# 1_V5.net
KiCad netlist of a schematic drawn in Altium Designer
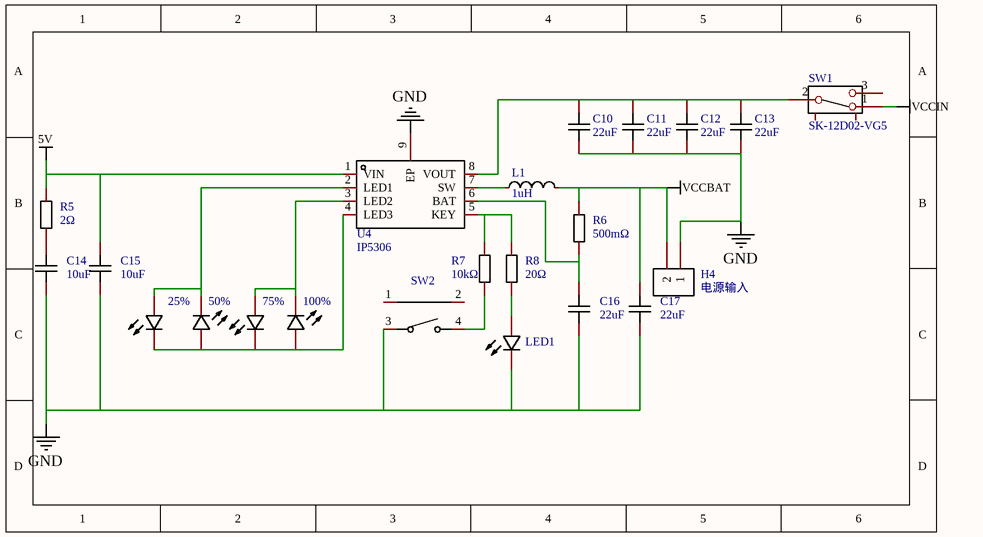
[diagram p0: 1_V5.schdoc]

(export (version "E")
  (design (tool "Eeschema 10.0.6"))
  (components
    (comp (ref "25%")
      (value "19-217/GHC-YR1S2/3T")
      (description "发光颜色:翠绿;二极管配置:-;主波长:520nm~535nm;色温:-;功率:110mW;安装方式:-;")
      (fields (field (name "MANUFACTURER") "EVERLIGHT(亿光)"))
      (libsource (lib "altium-import") (part "root_1_19-217/GHC-YR1S2/3T_"))
    )
    (comp (ref "50%")
      (value "19-217/GHC-YR1S2/3T")
      (description "发光颜色:翠绿;二极管配置:-;主波长:520nm~535nm;色温:-;功率:110mW;安装方式:-;")
      (fields (field (name "MANUFACTURER") "EVERLIGHT(亿光)"))
      (libsource (lib "altium-import") (part "root_3_19-217/GHC-YR1S2/3T_"))
    )
    (comp (ref "75%")
      (value "19-217/GHC-YR1S2/3T")
      (description "发光颜色:翠绿;二极管配置:-;主波长:520nm~535nm;色温:-;功率:110mW;安装方式:-;")
      (fields (field (name "MANUFACTURER") "EVERLIGHT(亿光)"))
      (libsource (lib "altium-import") (part "root_1_19-217/GHC-YR1S2/3T_"))
    )
    (comp (ref "100%")
      (value "19-217/GHC-YR1S2/3T")
      (description "发光颜色:翠绿;二极管配置:-;主波长:520nm~535nm;色温:-;功率:110mW;安装方式:-;")
      (fields (field (name "MANUFACTURER") "EVERLIGHT(亿光)"))
      (libsource (lib "altium-import") (part "root_3_19-217/GHC-YR1S2/3T_"))
    )
    (comp (ref "C10")
      (value "22uF")
      (description "容值:22uF;精度:±20%;额定电压:35V;材质(温度系数):X5R;")
      (fields
        (field (name "NAME") "22uF")
        (field (name "MANUFACTURER") "TDK")
        (field (name "MANUFACTURER PART") "C3216X5R1V226MTJ00E")
      )
      (libsource (lib "altium-import") (part "root_0_C3216X5R1V226MTJ00E_"))
    )
    (comp (ref "C11")
      (value "22uF")
      (description "容值:22uF;精度:±20%;额定电压:35V;材质(温度系数):X5R;")
      (fields
        (field (name "NAME") "22uF")
        (field (name "MANUFACTURER") "TDK")
        (field (name "MANUFACTURER PART") "C3216X5R1V226MTJ00E")
      )
      (libsource (lib "altium-import") (part "root_0_C3216X5R1V226MTJ00E_"))
    )
    (comp (ref "C12")
      (value "22uF")
      (description "容值:22uF;精度:±20%;额定电压:35V;材质(温度系数):X5R;")
      (fields
        (field (name "NAME") "22uF")
        (field (name "MANUFACTURER") "TDK")
        (field (name "MANUFACTURER PART") "C3216X5R1V226MTJ00E")
      )
      (libsource (lib "altium-import") (part "root_0_C3216X5R1V226MTJ00E_"))
    )
    (comp (ref "C13")
      (value "22uF")
      (description "容值:22uF;精度:±20%;额定电压:35V;材质(温度系数):X5R;")
      (fields
        (field (name "NAME") "22uF")
        (field (name "MANUFACTURER") "TDK")
        (field (name "MANUFACTURER PART") "C3216X5R1V226MTJ00E")
      )
      (libsource (lib "altium-import") (part "root_0_C3216X5R1V226MTJ00E_"))
    )
    (comp (ref "C14")
      (value "10uF")
      (description "容值:10uF;精度:±10%;额定电压:50V;材质(温度系数):X5R;")
      (fields
        (field (name "NAME") "10uF")
        (field (name "MANUFACTURER") "muRata(村田)")
        (field (name "MANUFACTURER PART") "GRM21BR61H106KE43L")
      )
      (libsource (lib "altium-import") (part "root_1_GRM21BR61H106KE43L_"))
    )
    (comp (ref "C15")
      (value "10uF")
      (description "容值:10uF;精度:±10%;额定电压:50V;材质(温度系数):X5R;")
      (fields
        (field (name "NAME") "10uF")
        (field (name "MANUFACTURER") "muRata(村田)")
        (field (name "MANUFACTURER PART") "GRM21BR61H106KE43L")
      )
      (libsource (lib "altium-import") (part "root_1_GRM21BR61H106KE43L_"))
    )
    (comp (ref "C16")
      (value "22uF")
      (description "容值:22uF;精度:±20%;额定电压:35V;材质(温度系数):X5R;")
      (fields
        (field (name "NAME") "22uF")
        (field (name "MANUFACTURER") "TDK")
        (field (name "MANUFACTURER PART") "C3216X5R1V226MTJ00E")
      )
      (libsource (lib "altium-import") (part "root_0_C3216X5R1V226MTJ00E_"))
    )
    (comp (ref "C17")
      (value "22uF")
      (description "容值:22uF;精度:±20%;额定电压:35V;材质(温度系数):X5R;")
      (fields
        (field (name "NAME") "22uF")
        (field (name "MANUFACTURER") "TDK")
        (field (name "MANUFACTURER PART") "C3216X5R1V226MTJ00E")
      )
      (libsource (lib "altium-import") (part "root_0_C3216X5R1V226MTJ00E_"))
    )
    (comp (ref "H4")
      (value "电源输入")
      (fields
        (field (name "NAME") "电源输入")
        (field (name "MANUFACTURER") "TE Connectivity(美国泰科)")
        (field (name "MANUFACTURER PART") "3-644456-2")
      )
      (libsource (lib "altium-import") (part "root_3_电源端口_"))
    )
    (comp (ref "L1")
      (value "1uH")
      (description "电感值:1uH;精度:±20%;额定电流:8.5A;饱和电流(Isat):14A;")
      (fields
        (field (name "NAME") "1uH")
        (field (name "MANUFACTURER") "cjiang(长江微电)")
        (field (name "MANUFACTURER PART") "FXL0618-1R0-M")
      )
      (libsource (lib "altium-import") (part "root_0_FXL0618-1R0-M_"))
    )
    (comp (ref "LED1")
      (value "19-217/GHC-YR1S2/3T")
      (description "发光颜色:翠绿;二极管配置:-;主波长:520nm~535nm;色温:-;功率:110mW;安装方式:-;")
      (fields (field (name "MANUFACTURER") "EVERLIGHT(亿光)"))
      (libsource (lib "altium-import") (part "root_1_19-217/GHC-YR1S2/3T_"))
    )
    (comp (ref "R5")
      (value "2Ω")
      (description "电阻类型:厚膜电阻;阻值:2Ω;精度:±1%;功率:125mW;")
      (fields
        (field (name "NAME") "2Ω")
        (field (name "MANUFACTURER") "UNI-ROYAL(厚声)")
        (field (name "MANUFACTURER PART") "0805W8F200KT5E")
      )
      (libsource (lib "altium-import") (part "root_1_0805W8F200KT5E_"))
    )
    (comp (ref "R6")
      (value "500mΩ")
      (description "电阻类型:厚膜电阻;阻值:500mΩ;精度:±1%;功率:250mW;")
      (fields
        (field (name "NAME") "500mΩ")
        (field (name "MANUFACTURER") "UNI-ROYAL(厚声)")
        (field (name "MANUFACTURER PART") "1206W4F500LT5E")
      )
      (libsource (lib "altium-import") (part "root_1_1206W4F500LT5E_"))
    )
    (comp (ref "R7")
      (value "10kΩ")
      (description "电阻类型:厚膜电阻;阻值:10kΩ;精度:±1%;功率:100mW;")
      (fields
        (field (name "NAME") "10kΩ")
        (field (name "MANUFACTURER") "UNI-ROYAL(厚声)")
        (field (name "MANUFACTURER PART") "0603WAF1002T5E")
      )
      (libsource (lib "altium-import") (part "root_1_0603WAF1002T5E_"))
    )
    (comp (ref "R8")
      (value "20Ω")
      (description "电阻类型:厚膜电阻;阻值:20Ω;精度:±1%;功率:100mW;")
      (fields
        (field (name "NAME") "20Ω")
        (field (name "MANUFACTURER") "UNI-ROYAL(厚声)")
        (field (name "MANUFACTURER PART") "0603WAF200JT5E")
      )
      (libsource (lib "altium-import") (part "root_1_0603WAF200JT5E_"))
    )
    (comp (ref "SW1")
      (value "SK-12D02-VG5")
      (fields (field (name "NAME") "SK-12D02-VG5") (field (name "MANUFACTURER") "韩国韩荣"))
      (libsource (lib "altium-import") (part "root_0_SK-12D02-VG5_C136722_"))
    )
    (comp (ref "SW2")
      (value "TS24CA")
      (description "触点电流:50mA;额定电压(DC):12V;电路结构:单刀单掷;安装方式:卧贴;带灯:-;机械寿命:-;")
      (fields (field (name "MANUFACTURER") "SHOU HAN(首韩)"))
      (libsource (lib "altium-import") (part "root_0_TS24CA_"))
    )
    (comp (ref "U4")
      (value "IP5306")
      (description "2.1A充电2.4A放电高集成度移动电源SOC")
      (fields (field (name "NAME") "IP5306") (field (name "MANUFACTURER") "INJOINIC(英集芯)"))
      (libsource (lib "altium-import") (part "root_0_IP5306_"))
    )
  )
  (nets
    (net (code "1") (name "5V") (class "Default")
      (node (ref "C15") (pin "2") (pinfunction "2_2") (pintype "passive"))
      (node (ref "R5") (pin "2") (pinfunction "2_2") (pintype "passive"))
      (node (ref "U4") (pin "1") (pinfunction "VIN_1") (pintype "passive"))
    )
    (net (code "2") (name "GND") (class "Default")
      (node (ref "C10") (pin "1") (pinfunction "1_1") (pintype "passive"))
      (node (ref "C11") (pin "1") (pinfunction "1_1") (pintype "passive"))
      (node (ref "C12") (pin "1") (pinfunction "1_1") (pintype "passive"))
      (node (ref "C13") (pin "1") (pinfunction "1_1") (pintype "passive"))
      (node (ref "C14") (pin "1") (pinfunction "1_1") (pintype "passive"))
      (node (ref "C15") (pin "1") (pinfunction "1_1") (pintype "passive"))
      (node (ref "C16") (pin "1") (pinfunction "1_1") (pintype "passive"))
      (node (ref "C17") (pin "1") (pinfunction "1_1") (pintype "passive"))
      (node (ref "H4") (pin "1") (pinfunction "1_1") (pintype "passive"))
      (node (ref "LED1") (pin "1") (pinfunction "C_1") (pintype "passive"))
      (node (ref "SW2") (pin "3") (pinfunction "3_3") (pintype "passive"))
      (node (ref "U4") (pin "9") (pinfunction "EP_9") (pintype "passive"))
    )
    (net (code "3") (name "Net-(25%-A)") (class "Default")
      (node (ref "25%") (pin "2") (pinfunction "A_2") (pintype "passive"))
      (node (ref "50%") (pin "1") (pinfunction "C_1") (pintype "passive"))
      (node (ref "U4") (pin "2") (pinfunction "LED1_2") (pintype "passive"))
    )
    (net (code "4") (name "Net-(100%-A)") (class "Default")
      (node (ref "100%") (pin "2") (pinfunction "A_2") (pintype "passive"))
      (node (ref "25%") (pin "1") (pinfunction "C_1") (pintype "passive"))
      (node (ref "50%") (pin "2") (pinfunction "A_2") (pintype "passive"))
      (node (ref "75%") (pin "1") (pinfunction "C_1") (pintype "passive"))
      (node (ref "U4") (pin "4") (pinfunction "LED3_4") (pintype "passive"))
    )
    (net (code "5") (name "Net-(100%-C)") (class "Default")
      (node (ref "100%") (pin "1") (pinfunction "C_1") (pintype "passive"))
      (node (ref "75%") (pin "2") (pinfunction "A_2") (pintype "passive"))
      (node (ref "U4") (pin "3") (pinfunction "LED2_3") (pintype "passive"))
    )
    (net (code "6") (name "Net-(C14-Pad2)") (class "Default")
      (node (ref "C14") (pin "2") (pinfunction "2_2") (pintype "passive"))
      (node (ref "R5") (pin "1") (pinfunction "1_1") (pintype "passive"))
    )
    (net (code "7") (name "Net-(LED1-A)") (class "Default")
      (node (ref "LED1") (pin "2") (pinfunction "A_2") (pintype "passive"))
      (node (ref "R8") (pin "1") (pinfunction "1_1") (pintype "passive"))
    )
    (net (code "8") (name "Net-(R7-Pad1)") (class "Default")
      (node (ref "R7") (pin "1") (pinfunction "1_1") (pintype "passive"))
      (node (ref "SW2") (pin "4") (pinfunction "4_4") (pintype "passive"))
    )
    (net (code "9") (name "Net-(U4-BAT)") (class "Default")
      (node (ref "C16") (pin "2") (pinfunction "2_2") (pintype "passive"))
      (node (ref "R6") (pin "1") (pinfunction "1_1") (pintype "passive"))
      (node (ref "U4") (pin "6") (pinfunction "BAT_6") (pintype "passive"))
    )
    (net (code "10") (name "Net-(U4-KEY)") (class "Default")
      (node (ref "R7") (pin "2") (pinfunction "2_2") (pintype "passive"))
      (node (ref "R8") (pin "2") (pinfunction "2_2") (pintype "passive"))
      (node (ref "U4") (pin "5") (pinfunction "KEY_5") (pintype "passive"))
    )
    (net (code "11") (name "Net-(U4-SW)") (class "Default")
      (node (ref "L1") (pin "1") (pinfunction "1_1") (pintype "passive"))
      (node (ref "U4") (pin "7") (pinfunction "SW_7") (pintype "passive"))
    )
    (net (code "12") (name "Net-(U4-VOUT)") (class "Default")
      (node (ref "C10") (pin "2") (pinfunction "2_2") (pintype "passive"))
      (node (ref "C11") (pin "2") (pinfunction "2_2") (pintype "passive"))
      (node (ref "C12") (pin "2") (pinfunction "2_2") (pintype "passive"))
      (node (ref "C13") (pin "2") (pinfunction "2_2") (pintype "passive"))
      (node (ref "SW1") (pin "2") (pinfunction "2_2") (pintype "passive"))
      (node (ref "U4") (pin "8") (pinfunction "VOUT_8") (pintype "passive"))
    )
    (net (code "13") (name "VCCBAT") (class "Default")
      (node (ref "C17") (pin "2") (pinfunction "2_2") (pintype "passive"))
      (node (ref "H4") (pin "2") (pinfunction "2_2") (pintype "passive"))
      (node (ref "L1") (pin "2") (pinfunction "2_2") (pintype "passive"))
      (node (ref "R6") (pin "2") (pinfunction "2_2") (pintype "passive"))
    )
    (net (code "14") (name "VCCIN") (class "Default")
      (node (ref "SW1") (pin "1") (pinfunction "1_1") (pintype "passive"))
    )
    (net (code "15") (name "unconnected-(SW1-Pad3)") (class "Default")
      (node (ref "SW1") (pin "3") (pinfunction "3_3") (pintype "passive"))
    )
    (net (code "16") (name "unconnected-(SW1-Pad4)") (class "Default")
      (node (ref "SW1") (pin "4") (pinfunction "4_4") (pintype "passive"))
    )
    (net (code "17") (name "unconnected-(SW1-Pad5)") (class "Default")
      (node (ref "SW1") (pin "5") (pinfunction "5_5") (pintype "passive"))
    )
    (net (code "18") (name "unconnected-(SW2-Pad1)") (class "Default")
      (node (ref "SW2") (pin "1") (pinfunction "1_1") (pintype "passive"))
    )
    (net (code "19") (name "unconnected-(SW2-Pad2)") (class "Default")
      (node (ref "SW2") (pin "2") (pinfunction "2_2") (pintype "passive"))
    )
  )
)
